# Input.net
KiCad netlist of a schematic drawn in Altium Designer
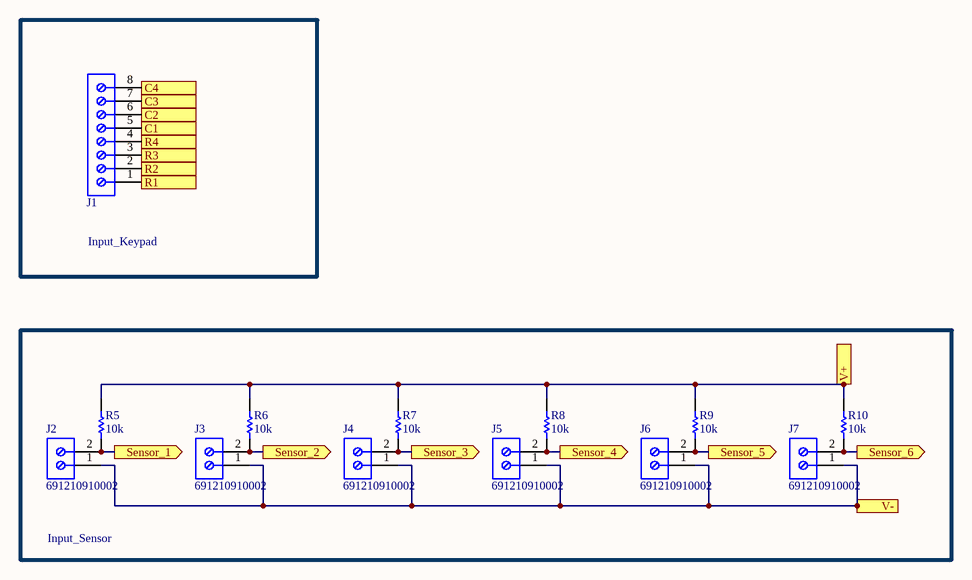
[diagram p0: Input.SchDoc]

(export (version "E")
  (design (tool "Eeschema 10.0.6"))
  (components
    (comp (ref "J1")
      (value "691210910008")
      (footprint "691210910008")
      (description "WR-TBL Series 2109 Horizontal Entry, Through Hole, pitch 2.54mm, 8p")
      (fields (field (name "MANUFACTURER") "Wurth Elektronik"))
      (libsource (lib "Altium_WR-TBL (rev22a)") (part "691210910008"))
    )
    (comp (ref "J2")
      (value "691210910002")
      (footprint "691210910002")
      (description "WR-TBL Serie 2109 Horizontal Entry, Rising Cage Clamp, pitch 2.54mm, 2p")
      (fields (field (name "PUBLISHER") "Wurth Elektronik"))
      (libsource (lib "691322310002.") (part "691210910002"))
    )
    (comp (ref "J3")
      (value "691210910002")
      (footprint "691210910002")
      (description "WR-TBL Serie 2109 Horizontal Entry, Rising Cage Clamp, pitch 2.54mm, 2p")
      (fields (field (name "PUBLISHER") "Wurth Elektronik"))
      (libsource (lib "691322310002.") (part "691210910002"))
    )
    (comp (ref "J4")
      (value "691210910002")
      (footprint "691210910002")
      (description "WR-TBL Serie 2109 Horizontal Entry, Rising Cage Clamp, pitch 2.54mm, 2p")
      (fields (field (name "PUBLISHER") "Wurth Elektronik"))
      (libsource (lib "691322310002.") (part "691210910002"))
    )
    (comp (ref "J5")
      (value "691210910002")
      (footprint "691210910002")
      (description "WR-TBL Serie 2109 Horizontal Entry, Rising Cage Clamp, pitch 2.54mm, 2p")
      (fields (field (name "PUBLISHER") "Wurth Elektronik"))
      (libsource (lib "691322310002.") (part "691210910002"))
    )
    (comp (ref "J6")
      (value "691210910002")
      (footprint "691210910002")
      (description "WR-TBL Serie 2109 Horizontal Entry, Rising Cage Clamp, pitch 2.54mm, 2p")
      (fields (field (name "PUBLISHER") "Wurth Elektronik"))
      (libsource (lib "691322310002.") (part "691210910002"))
    )
    (comp (ref "J7")
      (value "691210910002")
      (footprint "691210910002")
      (description "WR-TBL Serie 2109 Horizontal Entry, Rising Cage Clamp, pitch 2.54mm, 2p")
      (fields (field (name "PUBLISHER") "Wurth Elektronik"))
      (libsource (lib "691322310002.") (part "691210910002"))
    )
    (comp (ref "R5")
      (value "10k")
      (footprint "RES-SM-0603")
      (description "RES SMD 10K OHM 1% 1/4W 0603")
      (fields (field (name "MFR") "Rohm Semiconductor") (field (name "TOLERANCE") "±1%"))
      (libsource (lib "PIF_Library") (part "RESISTOR SMD"))
    )
    (comp (ref "R6")
      (value "10k")
      (footprint "RES-SM-0603")
      (description "RES SMD 10K OHM 1% 1/4W 0603")
      (fields (field (name "MFR") "Rohm Semiconductor") (field (name "TOLERANCE") "±1%"))
      (libsource (lib "PIF_Library") (part "RESISTOR SMD"))
    )
    (comp (ref "R7")
      (value "10k")
      (footprint "RES-SM-0603")
      (description "RES SMD 10K OHM 1% 1/4W 0603")
      (fields (field (name "MFR") "Rohm Semiconductor") (field (name "TOLERANCE") "±1%"))
      (libsource (lib "PIF_Library") (part "RESISTOR SMD"))
    )
    (comp (ref "R8")
      (value "10k")
      (footprint "RES-SM-0603")
      (description "RES SMD 10K OHM 1% 1/4W 0603")
      (fields (field (name "MFR") "Rohm Semiconductor") (field (name "TOLERANCE") "±1%"))
      (libsource (lib "PIF_Library") (part "RESISTOR SMD"))
    )
    (comp (ref "R9")
      (value "10k")
      (footprint "RES-SM-0603")
      (description "RES SMD 10K OHM 1% 1/4W 0603")
      (fields (field (name "MFR") "Rohm Semiconductor") (field (name "TOLERANCE") "±1%"))
      (libsource (lib "PIF_Library") (part "RESISTOR SMD"))
    )
    (comp (ref "R10")
      (value "10k")
      (footprint "RES-SM-0603")
      (description "RES SMD 10K OHM 1% 1/4W 0603")
      (fields (field (name "MFR") "Rohm Semiconductor") (field (name "TOLERANCE") "±1%"))
      (libsource (lib "PIF_Library") (part "RESISTOR SMD"))
    )
  )
  (nets
    (net (code "1") (name "/C1") (class "Default")
      (node (ref "J1") (pin "5") (pinfunction "5_5") (pintype "passive"))
    )
    (net (code "2") (name "/C2") (class "Default")
      (node (ref "J1") (pin "6") (pinfunction "6_6") (pintype "passive"))
    )
    (net (code "3") (name "/C3") (class "Default")
      (node (ref "J1") (pin "7") (pinfunction "7_7") (pintype "passive"))
    )
    (net (code "4") (name "/C4") (class "Default")
      (node (ref "J1") (pin "8") (pinfunction "8_8") (pintype "passive"))
    )
    (net (code "5") (name "/R1") (class "Default")
      (node (ref "J1") (pin "1") (pinfunction "1_1") (pintype "passive"))
    )
    (net (code "6") (name "/R2") (class "Default")
      (node (ref "J1") (pin "2") (pinfunction "2_2") (pintype "passive"))
    )
    (net (code "7") (name "/R3") (class "Default")
      (node (ref "J1") (pin "3") (pinfunction "3_3") (pintype "passive"))
    )
    (net (code "8") (name "/R4") (class "Default")
      (node (ref "J1") (pin "4") (pinfunction "4_4") (pintype "passive"))
    )
    (net (code "9") (name "/Sensor_1") (class "Default")
      (node (ref "J2") (pin "2") (pinfunction "2_2") (pintype "passive"))
      (node (ref "R5") (pin "1") (pinfunction "1_1") (pintype "passive"))
    )
    (net (code "10") (name "/Sensor_2") (class "Default")
      (node (ref "J3") (pin "2") (pinfunction "2_2") (pintype "passive"))
      (node (ref "R6") (pin "1") (pinfunction "1_1") (pintype "passive"))
    )
    (net (code "11") (name "/Sensor_3") (class "Default")
      (node (ref "J4") (pin "2") (pinfunction "2_2") (pintype "passive"))
      (node (ref "R7") (pin "1") (pinfunction "1_1") (pintype "passive"))
    )
    (net (code "12") (name "/Sensor_4") (class "Default")
      (node (ref "J5") (pin "2") (pinfunction "2_2") (pintype "passive"))
      (node (ref "R8") (pin "1") (pinfunction "1_1") (pintype "passive"))
    )
    (net (code "13") (name "/Sensor_5") (class "Default")
      (node (ref "J6") (pin "2") (pinfunction "2_2") (pintype "passive"))
      (node (ref "R9") (pin "1") (pinfunction "1_1") (pintype "passive"))
    )
    (net (code "14") (name "/Sensor_6") (class "Default")
      (node (ref "J7") (pin "2") (pinfunction "2_2") (pintype "passive"))
      (node (ref "R10") (pin "1") (pinfunction "1_1") (pintype "passive"))
    )
    (net (code "15") (name "/V+") (class "Default")
      (node (ref "R10") (pin "2") (pinfunction "2_2") (pintype "passive"))
      (node (ref "R5") (pin "2") (pinfunction "2_2") (pintype "passive"))
      (node (ref "R6") (pin "2") (pinfunction "2_2") (pintype "passive"))
      (node (ref "R7") (pin "2") (pinfunction "2_2") (pintype "passive"))
      (node (ref "R8") (pin "2") (pinfunction "2_2") (pintype "passive"))
      (node (ref "R9") (pin "2") (pinfunction "2_2") (pintype "passive"))
    )
    (net (code "16") (name "/V-") (class "Default")
      (node (ref "J2") (pin "1") (pinfunction "1_1") (pintype "passive"))
      (node (ref "J3") (pin "1") (pinfunction "1_1") (pintype "passive"))
      (node (ref "J4") (pin "1") (pinfunction "1_1") (pintype "passive"))
      (node (ref "J5") (pin "1") (pinfunction "1_1") (pintype "passive"))
      (node (ref "J6") (pin "1") (pinfunction "1_1") (pintype "passive"))
      (node (ref "J7") (pin "1") (pinfunction "1_1") (pintype "passive"))
    )
  )
)
